# Sheet5.net
KiCad netlist of a schematic drawn in Altium Designer
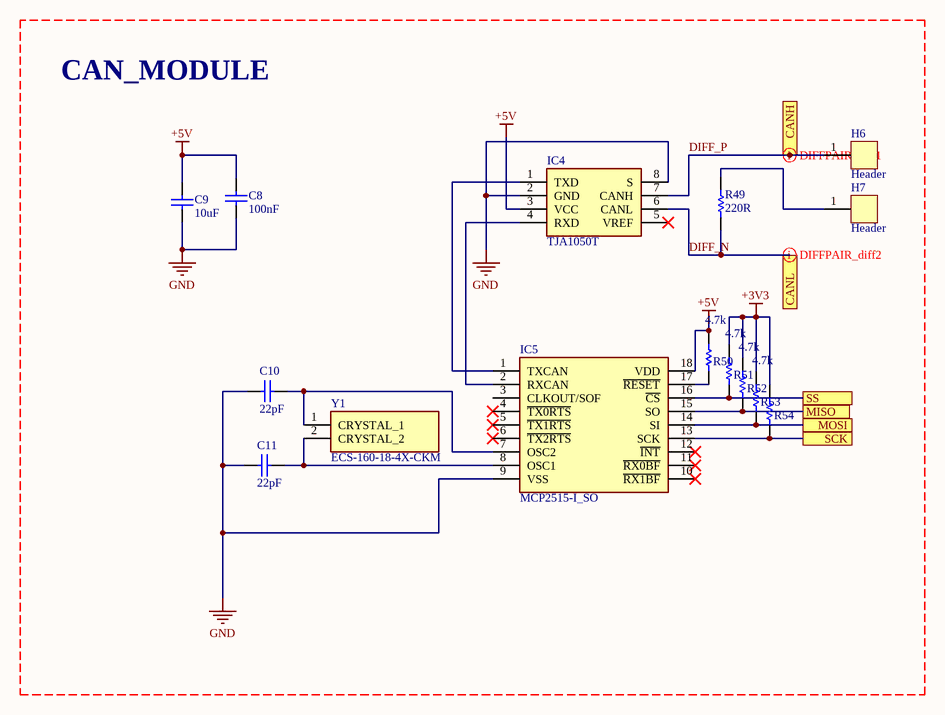
[diagram p0: Sheet5.SchDoc]

(export (version "E")
  (design (tool "Eeschema 10.0.6"))
  (components
    (comp (ref "C8")
      (value "100nF")
      (footprint "KEMT-1206-2_N")
      (description "CAP, Ceramic, 0.1 uF, +/- 10%, 50 V, -55 to 125 degC, 1206 (3216 Metric), RoHS, Tape and Reel")
      (fields (field (name "MANUFACTURER") "Kemet"))
      (libsource (lib "Schlib1") (part "CMP-1037-04202-2"))
    )
    (comp (ref "C9")
      (value "10uF")
      (footprint "KEMT-1206-2_N")
      (description "CAP, Ceramic, 0.1 uF, +/- 10%, 50 V, -55 to 125 degC, 1206 (3216 Metric), RoHS, Tape and Reel")
      (fields (field (name "MANUFACTURER") "Kemet"))
      (libsource (lib "Schlib1") (part "CMP-1037-04202-2"))
    )
    (comp (ref "C10")
      (value "22pF")
      (footprint "KEMT-1206-2_N")
      (description "CAP, Ceramic, 0.1 uF, +/- 10%, 50 V, -55 to 125 degC, 1206 (3216 Metric), RoHS, Tape and Reel")
      (fields (field (name "MANUFACTURER") "Kemet"))
      (libsource (lib "Schlib1") (part "CMP-1037-04202-2"))
    )
    (comp (ref "C11")
      (value "22pF")
      (footprint "KEMT-1206-2_N")
      (description "CAP, Ceramic, 0.1 uF, +/- 10%, 50 V, -55 to 125 degC, 1206 (3216 Metric), RoHS, Tape and Reel")
      (fields (field (name "MANUFACTURER") "Kemet"))
      (libsource (lib "Schlib1") (part "CMP-1037-04202-2"))
    )
    (comp (ref "H6") (value "Header") (footprint "Header") (libsource (lib "Schlib1") (part "Header")))
    (comp (ref "H7") (value "Header") (footprint "Header") (libsource (lib "Schlib1") (part "Header")))
    (comp (ref "IC4")
      (value "TJA1050T")
      (footprint "SamacSys:SOIC127P600X175-8N")
      (description "Integrated Circuit")
      (libsource (lib "*") (part "TJA1050T"))
    )
    (comp (ref "IC5")
      (value "MCP2515-I_SO")
      (footprint "SamacSys:SOIC127P1030X265-18N")
      (description "Integrated Circuit")
      (fields
        (field (name "MANUFACTURER_PART_NUMBER") "MCP2515-I/SO")
        (field (name "MOUSER PART NUMBER") "579-MCP2515-I/SO")
      )
      (libsource (lib "SamacSys") (part "MCP2515-I_SO"))
    )
    (comp (ref "R49")
      (value "220R")
      (footprint "R1206")
      (fields (field (name "PART NUMBER") "CRCW120647K0FKEA") (field (name "MANUFACTURER") "Vishay Dale"))
      (libsource (lib "SamacSys") (part "RES"))
    )
    (comp (ref "R50")
      (value "4.7k")
      (footprint "R1206")
      (fields (field (name "PART NUMBER") "CRCW120647K0FKEA") (field (name "MANUFACTURER") "Vishay Dale"))
      (libsource (lib "SamacSys") (part "RES"))
    )
    (comp (ref "R51")
      (value "4.7k")
      (footprint "R1206")
      (fields (field (name "PART NUMBER") "CRCW120647K0FKEA") (field (name "MANUFACTURER") "Vishay Dale"))
      (libsource (lib "SamacSys") (part "RES"))
    )
    (comp (ref "R52")
      (value "4.7k")
      (footprint "R1206")
      (fields (field (name "PART NUMBER") "CRCW120647K0FKEA") (field (name "MANUFACTURER") "Vishay Dale"))
      (libsource (lib "SamacSys") (part "RES"))
    )
    (comp (ref "R53")
      (value "4.7k")
      (footprint "R1206")
      (fields (field (name "PART NUMBER") "CRCW120647K0FKEA") (field (name "MANUFACTURER") "Vishay Dale"))
      (libsource (lib "SamacSys") (part "RES"))
    )
    (comp (ref "R54")
      (value "4.7k")
      (footprint "R1206")
      (fields (field (name "PART NUMBER") "CRCW120647K0FKEA") (field (name "MANUFACTURER") "Vishay Dale"))
      (libsource (lib "SamacSys") (part "RES"))
    )
    (comp (ref "Y1")
      (value "ECS-160-18-4X-CKM")
      (footprint "SamacSys:ECS160184XCKM")
      (description "Crystal or Oscillator")
      (fields (field (name "MOUSER PART NUMBER") "520-ECS160-18-4X-CKM"))
      (libsource (lib "SamacSys") (part "ECS-160-18-4X-CKM"))
    )
  )
  (nets
    (net (code "1") (name "+3V3") (class "Default")
      (node (ref "R51") (pin "1") (pinfunction "1_1") (pintype "passive"))
      (node (ref "R52") (pin "1") (pinfunction "1_1") (pintype "passive"))
      (node (ref "R53") (pin "1") (pinfunction "1_1") (pintype "passive"))
      (node (ref "R54") (pin "1") (pinfunction "1_1") (pintype "passive"))
    )
    (net (code "2") (name "+5V") (class "Default")
      (node (ref "C8") (pin "1") (pinfunction "1_1") (pintype "passive"))
      (node (ref "C9") (pin "1") (pinfunction "1_1") (pintype "passive"))
      (node (ref "IC4") (pin "3") (pinfunction "VCC_3") (pintype "passive"))
      (node (ref "IC5") (pin "18") (pinfunction "VDD_18") (pintype "passive"))
      (node (ref "R50") (pin "1") (pinfunction "1_1") (pintype "passive"))
    )
    (net (code "3") (name "/DIFF_N") (class "Default")
      (node (ref "IC4") (pin "6") (pinfunction "CANL_6") (pintype "passive"))
      (node (ref "R49") (pin "1") (pinfunction "1_1") (pintype "passive"))
    )
    (net (code "4") (name "/DIFF_P") (class "Default")
      (node (ref "H6") (pin "1") (pinfunction "1_1") (pintype "passive"))
      (node (ref "IC4") (pin "7") (pinfunction "CANH_7") (pintype "passive"))
    )
    (net (code "5") (name "/MISO") (class "Default")
      (node (ref "IC5") (pin "15") (pinfunction "SO_15") (pintype "passive"))
      (node (ref "R52") (pin "2") (pinfunction "2_2") (pintype "passive"))
    )
    (net (code "6") (name "/MOSI") (class "Default")
      (node (ref "IC5") (pin "14") (pinfunction "SI_14") (pintype "passive"))
      (node (ref "R53") (pin "2") (pinfunction "2_2") (pintype "passive"))
    )
    (net (code "7") (name "/SCK") (class "Default")
      (node (ref "IC5") (pin "13") (pinfunction "SCK_13") (pintype "passive"))
      (node (ref "R54") (pin "2") (pinfunction "2_2") (pintype "passive"))
    )
    (net (code "8") (name "/SS") (class "Default")
      (node (ref "IC5") (pin "16") (pinfunction "~{CS}_16") (pintype "passive"))
      (node (ref "R51") (pin "2") (pinfunction "2_2") (pintype "passive"))
    )
    (net (code "9") (name "GND") (class "Default")
      (node (ref "C10") (pin "2") (pinfunction "2_2") (pintype "passive"))
      (node (ref "C11") (pin "2") (pinfunction "2_2") (pintype "passive"))
      (node (ref "C8") (pin "2") (pinfunction "2_2") (pintype "passive"))
      (node (ref "C9") (pin "2") (pinfunction "2_2") (pintype "passive"))
      (node (ref "IC4") (pin "2") (pinfunction "GND_2") (pintype "passive"))
      (node (ref "IC4") (pin "8") (pinfunction "S_8") (pintype "passive"))
      (node (ref "IC5") (pin "9") (pinfunction "VSS_9") (pintype "passive"))
    )
    (net (code "10") (name "Net-(H7-Pad1)") (class "Default")
      (node (ref "H7") (pin "1") (pinfunction "1_1") (pintype "passive"))
      (node (ref "R49") (pin "2") (pinfunction "2_2") (pintype "passive"))
    )
    (net (code "11") (name "Net-(IC4-RXD)") (class "Default")
      (node (ref "IC4") (pin "4") (pinfunction "RXD_4") (pintype "passive"))
      (node (ref "IC5") (pin "2") (pinfunction "RXCAN_2") (pintype "passive"))
    )
    (net (code "12") (name "Net-(IC4-TXD)") (class "Default")
      (node (ref "IC4") (pin "1") (pinfunction "TXD_1") (pintype "passive"))
      (node (ref "IC5") (pin "1") (pinfunction "TXCAN_1") (pintype "passive"))
    )
    (net (code "13") (name "Net-(IC5-OSC1)") (class "Default")
      (node (ref "C11") (pin "1") (pinfunction "1_1") (pintype "passive"))
      (node (ref "IC5") (pin "8") (pinfunction "OSC1_8") (pintype "passive"))
      (node (ref "Y1") (pin "2") (pinfunction "CRYSTAL_2_2") (pintype "passive"))
    )
    (net (code "14") (name "Net-(IC5-OSC2)") (class "Default")
      (node (ref "C10") (pin "1") (pinfunction "1_1") (pintype "passive"))
      (node (ref "IC5") (pin "7") (pinfunction "OSC2_7") (pintype "passive"))
      (node (ref "Y1") (pin "1") (pinfunction "CRYSTAL_1_1") (pintype "passive"))
    )
    (net (code "15") (name "Net-(IC5-~{RESET})") (class "Default")
      (node (ref "IC5") (pin "17") (pinfunction "~{RESET}_17") (pintype "passive"))
      (node (ref "R50") (pin "2") (pinfunction "2_2") (pintype "passive"))
    )
    (net (code "16") (name "unconnected-(IC4-VREF-Pad5)") (class "Default")
      (node (ref "IC4") (pin "5") (pinfunction "VREF_5") (pintype "passive+no_connect"))
    )
    (net (code "17") (name "unconnected-(IC5-CLKOUT{slash}SOF-Pad3)") (class "Default")
      (node (ref "IC5") (pin "3") (pinfunction "CLKOUT/SOF_3") (pintype "passive"))
    )
    (net (code "18") (name "unconnected-(IC5-~{INT}-Pad12)") (class "Default")
      (node (ref "IC5") (pin "12") (pinfunction "~{INT}_12") (pintype "passive+no_connect"))
    )
    (net (code "19") (name "unconnected-(IC5-~{RX0BF}-Pad11)") (class "Default")
      (node (ref "IC5") (pin "11") (pinfunction "~{RX0BF}_11") (pintype "passive+no_connect"))
    )
    (net (code "20") (name "unconnected-(IC5-~{RX1BF}-Pad10)") (class "Default")
      (node (ref "IC5") (pin "10") (pinfunction "~{RX1BF}_10") (pintype "passive+no_connect"))
    )
    (net (code "21") (name "unconnected-(IC5-~{TX0RTS}-Pad4)") (class "Default")
      (node (ref "IC5") (pin "4") (pinfunction "~{TX0RTS}_4") (pintype "passive+no_connect"))
    )
    (net (code "22") (name "unconnected-(IC5-~{TX1RTS}-Pad5)") (class "Default")
      (node (ref "IC5") (pin "5") (pinfunction "~{TX1RTS}_5") (pintype "passive+no_connect"))
    )
    (net (code "23") (name "unconnected-(IC5-~{TX2RTS}-Pad6)") (class "Default")
      (node (ref "IC5") (pin "6") (pinfunction "~{TX2RTS}_6") (pintype "passive+no_connect"))
    )
  )
)
